# SCH_555-led-chaser_2025-11-01.net
KiCad netlist of a schematic drawn in EasyEDA
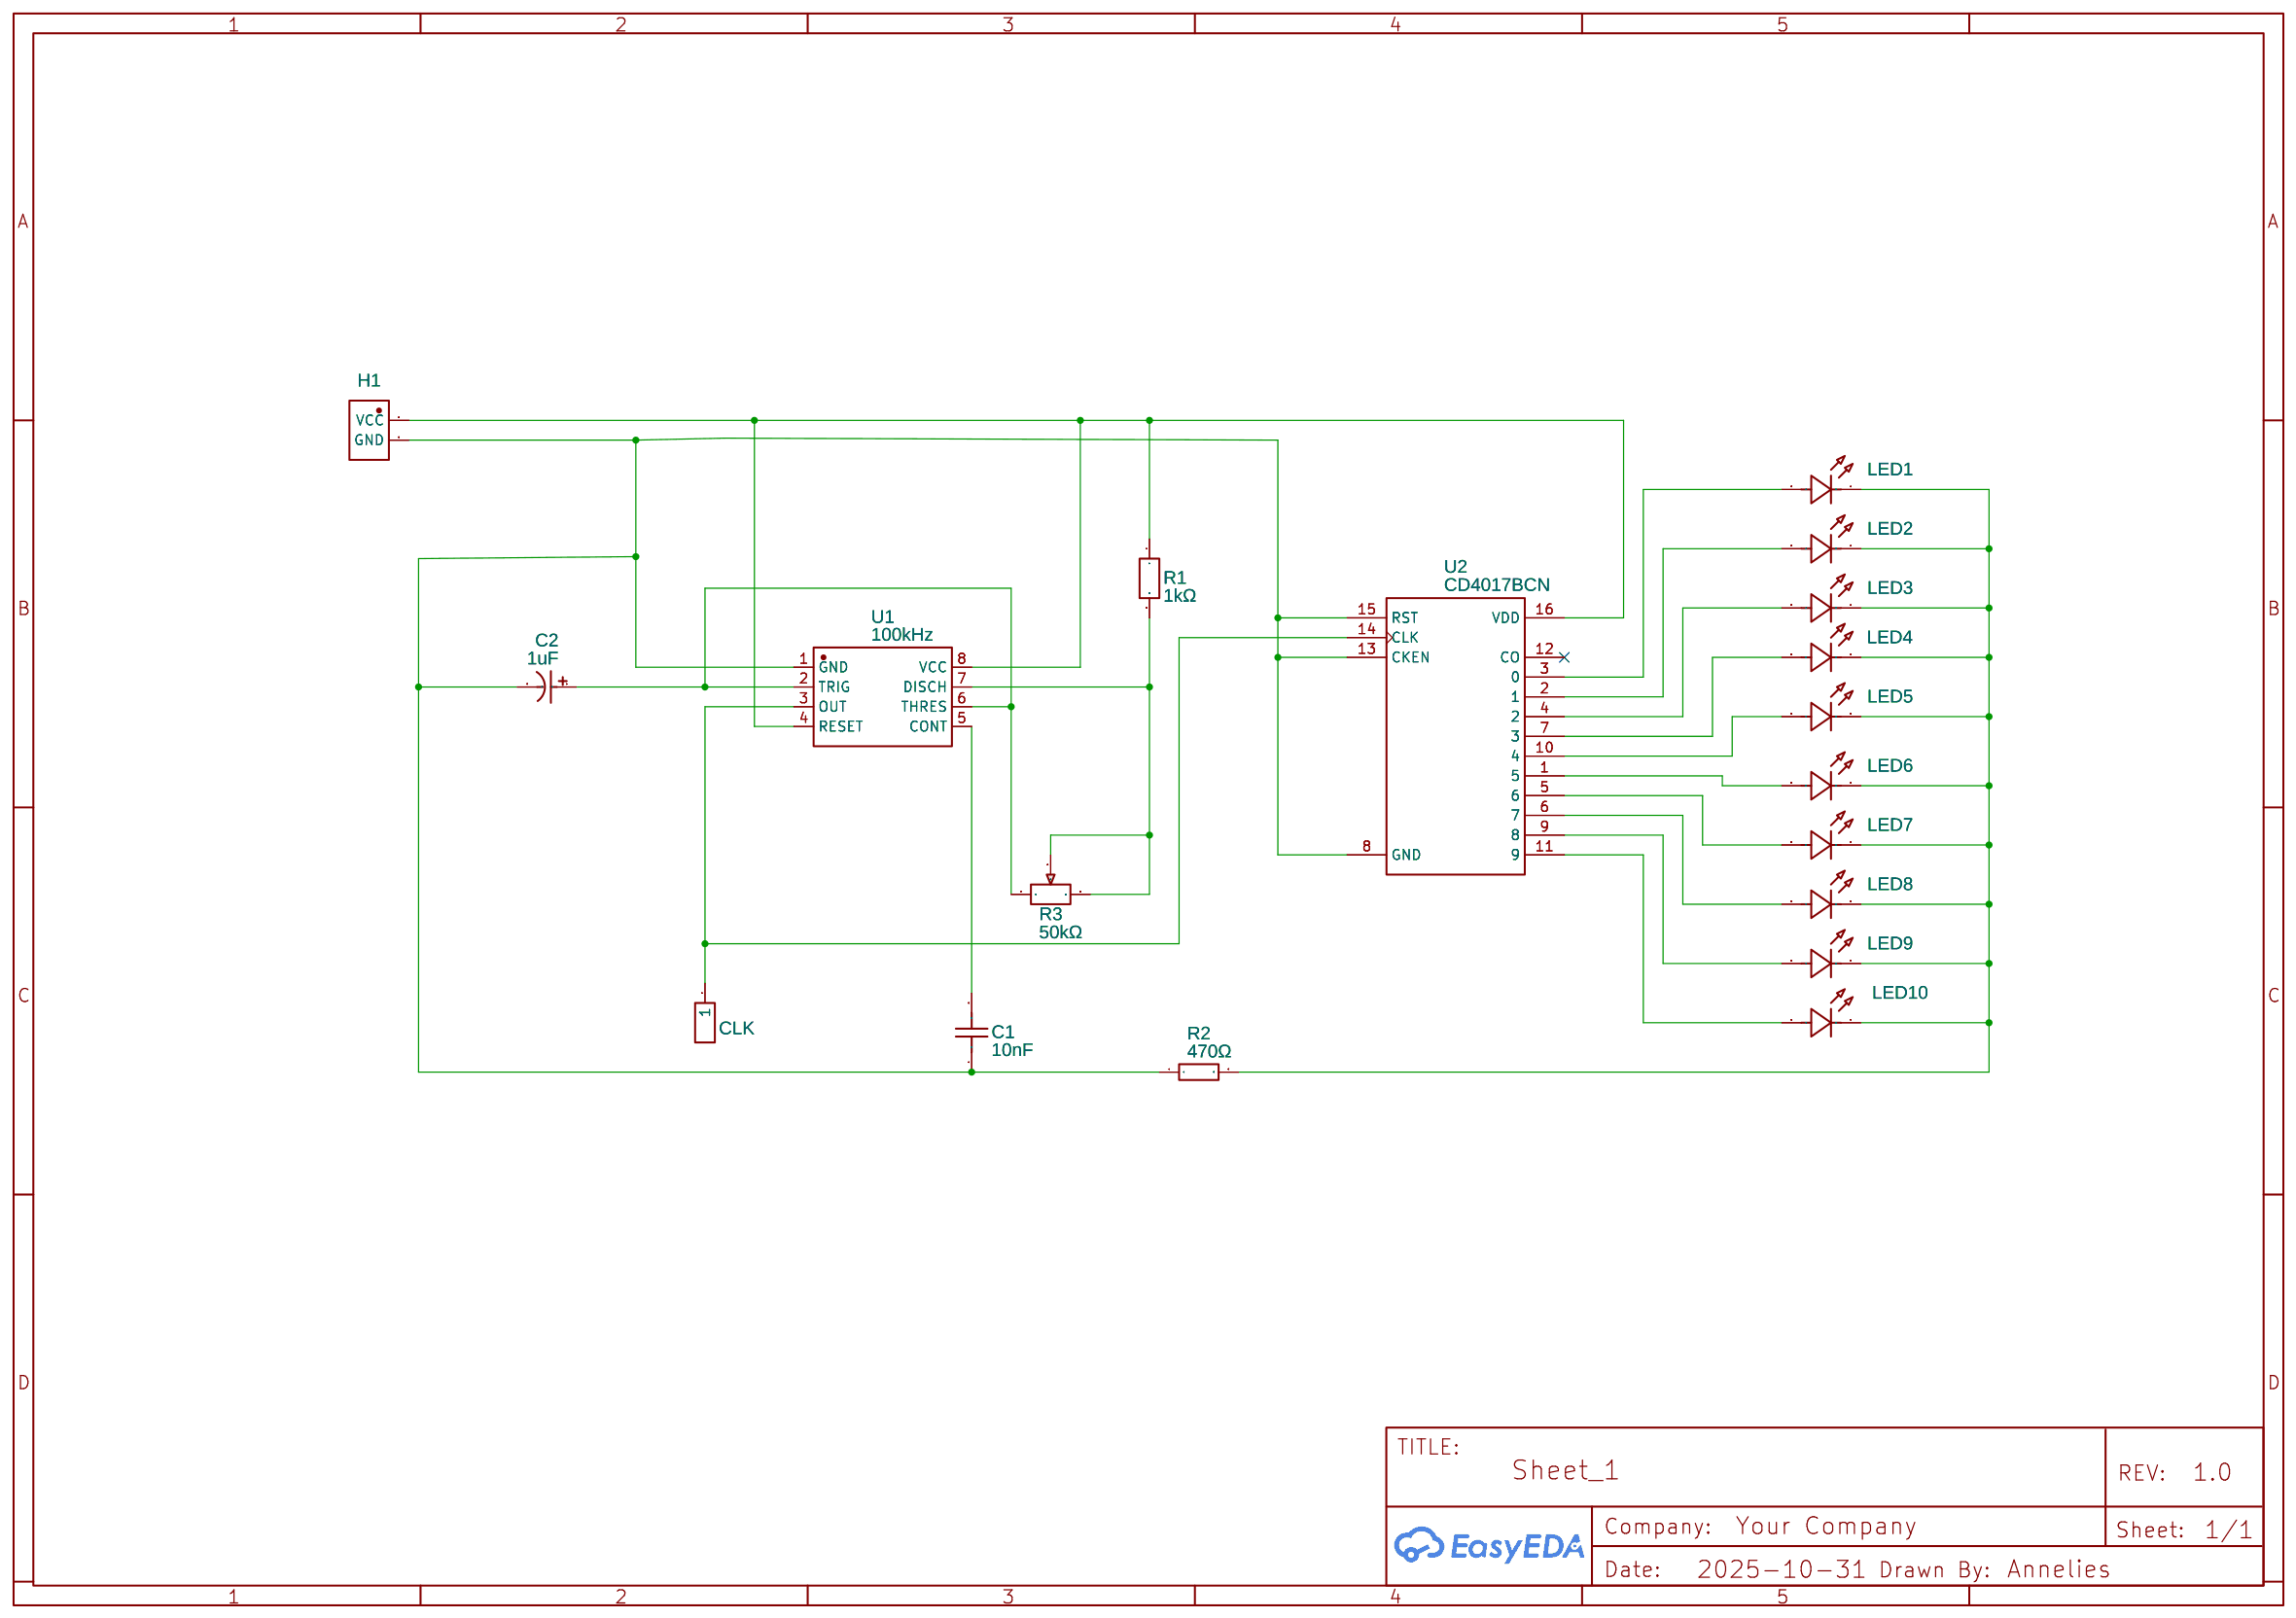
[diagram p0: schematic sheet]

(export (version "E")
  (design (tool "Eeschema 10.0.6"))
  (components
    (comp (ref "C1")
      (value "10nF")
      (fields (field (name "Manufacturer Part") "N09F1B103MN0B0S0N0") (field (name "Manufacturer") "STE(松田)"))
      (libsource (lib "") (part "N09F1B103MN0B0S0N0"))
    )
    (comp (ref "C2")
      (value "1uF")
      (fields (field (name "Manufacturer Part") "KF010M050C110A") (field (name "Manufacturer") "CapXon(丰宾)"))
      (libsource (lib "") (part "KF010M050C110A"))
    )
    (comp (ref "CLK")
      (value "CLK")
      (fields (field (name "Manufacturer Part") "2.54-1*1P针") (field (name "Manufacturer") "BOOMELE(博穆精密)"))
      (libsource (lib "") (part "Header-Male-2.54_1x1"))
    )
    (comp (ref "H1")
      (value "PZ254V-11-02P")
      (fields (field (name "Manufacturer") "XFCN(兴飞)"))
      (libsource (lib "") (part "PZ254V-11-02P"))
    )
    (comp (ref "LED1")
      (value "XL-502UWC")
      (fields (field (name "Manufacturer") "XINGLIGHT(成兴光)"))
      (libsource (lib "") (part "XL-502UWC"))
    )
    (comp (ref "LED2")
      (value "XL-502UWC")
      (fields (field (name "Manufacturer") "XINGLIGHT(成兴光)"))
      (libsource (lib "") (part "XL-502UWC"))
    )
    (comp (ref "LED3")
      (value "XL-502UWC")
      (fields (field (name "Manufacturer") "XINGLIGHT(成兴光)"))
      (libsource (lib "") (part "XL-502UWC"))
    )
    (comp (ref "LED4")
      (value "XL-502UWC")
      (fields (field (name "Manufacturer") "XINGLIGHT(成兴光)"))
      (libsource (lib "") (part "XL-502UWC"))
    )
    (comp (ref "LED5")
      (value "XL-502UWC")
      (fields (field (name "Manufacturer") "XINGLIGHT(成兴光)"))
      (libsource (lib "") (part "XL-502UWC"))
    )
    (comp (ref "LED6")
      (value "XL-502UWC")
      (fields (field (name "Manufacturer") "XINGLIGHT(成兴光)"))
      (libsource (lib "") (part "XL-502UWC"))
    )
    (comp (ref "LED7")
      (value "XL-502UWC")
      (fields (field (name "Manufacturer") "XINGLIGHT(成兴光)"))
      (libsource (lib "") (part "XL-502UWC"))
    )
    (comp (ref "LED8")
      (value "XL-502UWC")
      (fields (field (name "Manufacturer") "XINGLIGHT(成兴光)"))
      (libsource (lib "") (part "XL-502UWC"))
    )
    (comp (ref "LED9")
      (value "XL-502UWC")
      (fields (field (name "Manufacturer") "XINGLIGHT(成兴光)"))
      (libsource (lib "") (part "XL-502UWC"))
    )
    (comp (ref "LED10")
      (value "XL-502UWC")
      (fields (field (name "Manufacturer") "XINGLIGHT(成兴光)"))
      (libsource (lib "") (part "XL-502UWC"))
    )
    (comp (ref "R1")
      (value "1kΩ")
      (fields (field (name "Manufacturer Part") "MF1/4W-1KΩ±1%T52") (field (name "Manufacturer") "华星机电"))
      (libsource (lib "") (part "MF1/4W-1KΩ±1%T52"))
    )
    (comp (ref "R2")
      (value "470Ω")
      (fields
        (field (name "Manufacturer Part") "MFR0W4F4700A50")
        (field (name "Manufacturer") "UNI-ROYAL(厚声)")
      )
      (libsource (lib "") (part "MFR0W4F4700A50"))
    )
    (comp (ref "R3")
      (value "50kΩ")
      (fields (field (name "Manufacturer Part") "3296X-1-503") (field (name "Manufacturer") "BOCHEN(博晨)"))
      (libsource (lib "") (part "3296X-1-503_C118912"))
    )
    (comp (ref "U1")
      (value "100kHz")
      (fields (field (name "Manufacturer Part") "NE555P") (field (name "Manufacturer") "TI(德州仪器)"))
      (libsource (lib "") (part "NE555P"))
    )
    (comp (ref "U2") (value "CD4017BCN") (libsource (lib "") (part "CD4017BCN")))
  )
  (nets
    (net (code "1") (name "Net-(H1-GND)") (class "Default")
      (node (ref "C1") (pin "1") (pinfunction "1_1") (pintype "unspecified"))
      (node (ref "C2") (pin "2") (pinfunction "2_2") (pintype "input"))
      (node (ref "H1") (pin "2") (pinfunction "GND_2") (pintype "unspecified"))
      (node (ref "R2") (pin "1") (pinfunction "1_1") (pintype "input"))
      (node (ref "U1") (pin "1") (pinfunction "GND_1") (pintype "unspecified"))
      (node (ref "U2") (pin "13") (pinfunction "CKEN_13") (pintype "unspecified"))
      (node (ref "U2") (pin "15") (pinfunction "RST_15") (pintype "unspecified"))
      (node (ref "U2") (pin "8") (pinfunction "GND_8") (pintype "passive"))
    )
    (net (code "2") (name "Net-(H1-VCC)") (class "Default")
      (node (ref "H1") (pin "1") (pinfunction "VCC_1") (pintype "unspecified"))
      (node (ref "R1") (pin "1") (pinfunction "1_1") (pintype "unspecified"))
      (node (ref "U1") (pin "4") (pinfunction "RESET_4") (pintype "unspecified"))
      (node (ref "U1") (pin "8") (pinfunction "VCC_8") (pintype "unspecified"))
      (node (ref "U2") (pin "16") (pinfunction "VDD_16") (pintype "passive"))
    )
    (net (code "3") (name "Net-(LED1-A)") (class "Default")
      (node (ref "LED1") (pin "2") (pinfunction "A_2") (pintype "unspecified"))
      (node (ref "U2") (pin "3") (pinfunction "0_3") (pintype "output"))
    )
    (net (code "4") (name "Net-(LED1-K)") (class "Default")
      (node (ref "LED1") (pin "1") (pinfunction "K_1") (pintype "unspecified"))
      (node (ref "LED10") (pin "1") (pinfunction "K_1") (pintype "unspecified"))
      (node (ref "LED2") (pin "1") (pinfunction "K_1") (pintype "unspecified"))
      (node (ref "LED3") (pin "1") (pinfunction "K_1") (pintype "unspecified"))
      (node (ref "LED4") (pin "1") (pinfunction "K_1") (pintype "unspecified"))
      (node (ref "LED5") (pin "1") (pinfunction "K_1") (pintype "unspecified"))
      (node (ref "LED6") (pin "1") (pinfunction "K_1") (pintype "unspecified"))
      (node (ref "LED7") (pin "1") (pinfunction "K_1") (pintype "unspecified"))
      (node (ref "LED8") (pin "1") (pinfunction "K_1") (pintype "unspecified"))
      (node (ref "LED9") (pin "1") (pinfunction "K_1") (pintype "unspecified"))
      (node (ref "R2") (pin "2") (pinfunction "2_2") (pintype "input"))
    )
    (net (code "5") (name "Net-(LED2-A)") (class "Default")
      (node (ref "LED2") (pin "2") (pinfunction "A_2") (pintype "unspecified"))
      (node (ref "U2") (pin "2") (pinfunction "1_2") (pintype "output"))
    )
    (net (code "6") (name "Net-(LED3-A)") (class "Default")
      (node (ref "LED3") (pin "2") (pinfunction "A_2") (pintype "unspecified"))
      (node (ref "U2") (pin "4") (pinfunction "2_4") (pintype "output"))
    )
    (net (code "7") (name "Net-(LED4-A)") (class "Default")
      (node (ref "LED4") (pin "2") (pinfunction "A_2") (pintype "unspecified"))
      (node (ref "U2") (pin "7") (pinfunction "3_7") (pintype "output"))
    )
    (net (code "8") (name "Net-(LED5-A)") (class "Default")
      (node (ref "LED5") (pin "2") (pinfunction "A_2") (pintype "unspecified"))
      (node (ref "U2") (pin "10") (pinfunction "4_10") (pintype "output"))
    )
    (net (code "9") (name "Net-(LED6-A)") (class "Default")
      (node (ref "LED6") (pin "2") (pinfunction "A_2") (pintype "unspecified"))
      (node (ref "U2") (pin "1") (pinfunction "5_1") (pintype "output"))
    )
    (net (code "10") (name "Net-(LED7-A)") (class "Default")
      (node (ref "LED7") (pin "2") (pinfunction "A_2") (pintype "unspecified"))
      (node (ref "U2") (pin "5") (pinfunction "6_5") (pintype "output"))
    )
    (net (code "11") (name "Net-(LED8-A)") (class "Default")
      (node (ref "LED8") (pin "2") (pinfunction "A_2") (pintype "unspecified"))
      (node (ref "U2") (pin "6") (pinfunction "7_6") (pintype "output"))
    )
    (net (code "12") (name "Net-(LED9-A)") (class "Default")
      (node (ref "LED9") (pin "2") (pinfunction "A_2") (pintype "unspecified"))
      (node (ref "U2") (pin "9") (pinfunction "8_9") (pintype "output"))
    )
    (net (code "13") (name "Net-(LED10-A)") (class "Default")
      (node (ref "LED10") (pin "2") (pinfunction "A_2") (pintype "unspecified"))
      (node (ref "U2") (pin "11") (pinfunction "9_11") (pintype "output"))
    )
    (net (code "14") (name "Net-(U1-CONT)") (class "Default")
      (node (ref "C1") (pin "2") (pinfunction "2_2") (pintype "unspecified"))
      (node (ref "U1") (pin "5") (pinfunction "CONT_5") (pintype "unspecified"))
    )
    (net (code "15") (name "Net-(U1-DISCH)") (class "Default")
      (node (ref "R1") (pin "2") (pinfunction "2_2") (pintype "unspecified"))
      (node (ref "R3") (pin "2") (pinfunction "2_2") (pintype "input"))
      (node (ref "R3") (pin "3") (pinfunction "3_3") (pintype "input"))
      (node (ref "U1") (pin "7") (pinfunction "DISCH_7") (pintype "unspecified"))
    )
    (net (code "16") (name "Net-(U1-OUT)") (class "Default")
      (node (ref "CLK") (pin "1") (pinfunction "1_1") (pintype "input"))
      (node (ref "U1") (pin "3") (pinfunction "OUT_3") (pintype "unspecified"))
      (node (ref "U2") (pin "14") (pinfunction "CLK_14") (pintype "unspecified"))
    )
    (net (code "17") (name "Net-(U1-THRES)") (class "Default")
      (node (ref "C2") (pin "1") (pinfunction "1_1") (pintype "input"))
      (node (ref "R3") (pin "1") (pinfunction "1_1") (pintype "input"))
      (node (ref "U1") (pin "2") (pinfunction "TRIG_2") (pintype "unspecified"))
      (node (ref "U1") (pin "6") (pinfunction "THRES_6") (pintype "unspecified"))
    )
    (net (code "18") (name "unconnected-(U2-CO-Pad12)") (class "Default")
      (node (ref "U2") (pin "12") (pinfunction "CO_12") (pintype "output+no_connect"))
    )
  )
)
